# 1_XBEE_Interface.net
KiCad netlist of a schematic drawn in Altium Designer
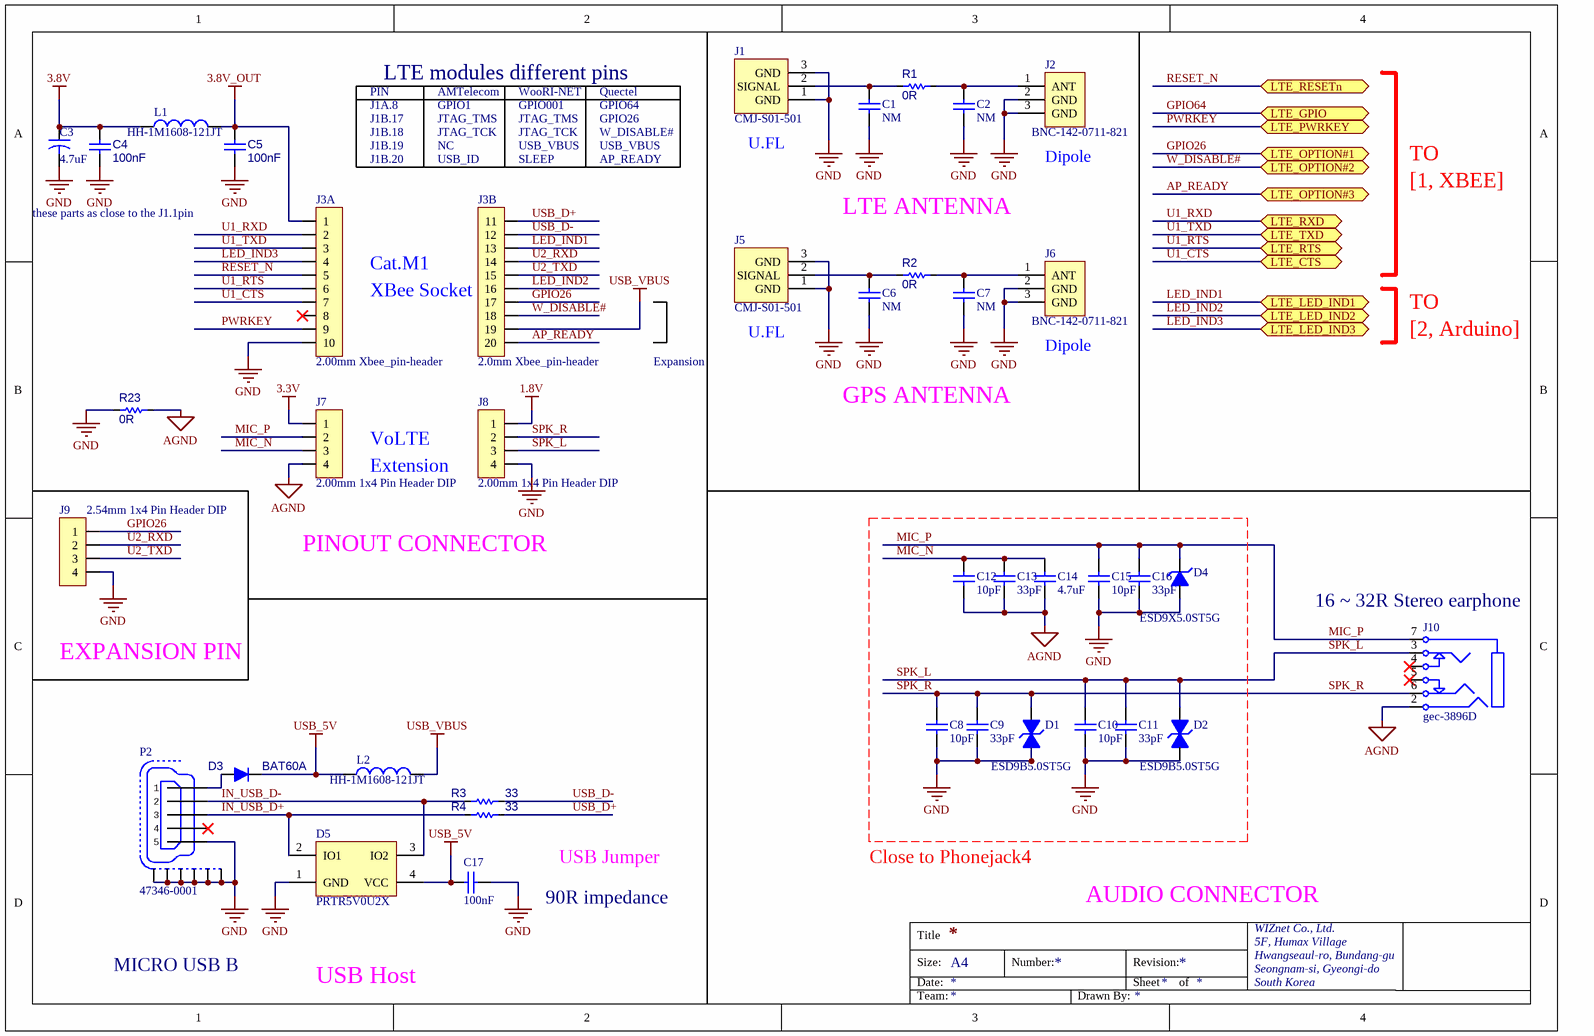
[diagram p0: 1.XBEE Interface.SchDoc]

(export (version "E")
  (design (tool "Eeschema 10.0.6"))
  (components
    (comp (ref "C1")
      (value "NM")
      (footprint "CAP-0402")
      (description "Ceramic CAP 0402(1005)")
      (libsource (lib "Edward") (part "CAP-0402"))
    )
    (comp (ref "C2")
      (value "NM")
      (footprint "CAP-0402")
      (description "Ceramic CAP 0402(1005)")
      (libsource (lib "Edward") (part "CAP-0402"))
    )
    (comp (ref "C3")
      (value "4.7uF")
      (footprint "CAP-A Size")
      (description "Electrolytic Capacitors")
      (libsource (lib "Quectel_IF_Board") (part "CAP"))
    )
    (comp (ref "C4")
      (value "100nF")
      (footprint "CAP-0603")
      (description "Ceramic CAP 0603(1608)")
      (libsource (lib "Scott_lib") (part "CAP-0603"))
    )
    (comp (ref "C5")
      (value "100nF")
      (footprint "CAP-0603")
      (description "Ceramic CAP 0603(1608)")
      (libsource (lib "Scott_lib") (part "CAP-0603"))
    )
    (comp (ref "C6")
      (value "NM")
      (footprint "CAP-0402")
      (description "Ceramic CAP 0402(1005)")
      (libsource (lib "Edward") (part "CAP-0402"))
    )
    (comp (ref "C7")
      (value "NM")
      (footprint "CAP-0402")
      (description "Ceramic CAP 0402(1005)")
      (libsource (lib "Edward") (part "CAP-0402"))
    )
    (comp (ref "C8")
      (value "10pF")
      (footprint "CAP-0402")
      (description "Ceramic CAP 0402(1005)")
      (libsource (lib "Edward") (part "CAP-0402"))
    )
    (comp (ref "C9")
      (value "33pF")
      (footprint "CAP-0402")
      (description "Ceramic CAP 0402(1005)")
      (libsource (lib "Edward") (part "CAP-0402"))
    )
    (comp (ref "C10")
      (value "10pF")
      (footprint "CAP-0402")
      (description "Ceramic CAP 0402(1005)")
      (libsource (lib "Edward") (part "CAP-0402"))
    )
    (comp (ref "C11")
      (value "33pF")
      (footprint "CAP-0402")
      (description "Ceramic CAP 0402(1005)")
      (libsource (lib "Edward") (part "CAP-0402"))
    )
    (comp (ref "C12")
      (value "10pF")
      (footprint "CAP-0402")
      (description "Ceramic CAP 0402(1005)")
      (libsource (lib "Edward") (part "CAP-0402"))
    )
    (comp (ref "C13")
      (value "33pF")
      (footprint "CAP-0402")
      (description "Ceramic CAP 0402(1005)")
      (libsource (lib "Edward") (part "CAP-0402"))
    )
    (comp (ref "C14")
      (value "4.7uF")
      (footprint "CAP-0603")
      (description "Ceramic CAP 0603(1608)")
      (libsource (lib "Edward") (part "CAP-0603"))
    )
    (comp (ref "C15")
      (value "10pF")
      (footprint "CAP-0402")
      (description "Ceramic CAP 0402(1005)")
      (libsource (lib "Edward") (part "CAP-0402"))
    )
    (comp (ref "C16")
      (value "33pF")
      (footprint "CAP-0402")
      (description "Ceramic CAP 0402(1005)")
      (libsource (lib "Edward") (part "CAP-0402"))
    )
    (comp (ref "C17")
      (value "100nF")
      (footprint "CAP-0402")
      (description "Ceramic CAP 0402")
      (libsource (lib "Scott_lib") (part "CAP-0805"))
    )
    (comp (ref "D1")
      (value "ESD9B5.0ST5G")
      (footprint "SOD-882(TVS)")
      (description "Bi-directional TVS diode")
      (libsource (lib "Edward") (part "PESD5V0S1BL"))
    )
    (comp (ref "D2")
      (value "ESD9B5.0ST5G")
      (footprint "SOD-882(TVS)")
      (description "Bi-directional TVS diode")
      (libsource (lib "Edward") (part "PESD5V0S1BL"))
    )
    (comp (ref "D3")
      (value "BAT60A")
      (footprint "SOD-323(1-C,2-A)")
      (description "Silicon Schottky Diode")
      (libsource (lib "Scott_lib") (part "DIODE-BAT60A"))
    )
    (comp (ref "D4")
      (value "ESD9X5.0ST5G")
      (footprint "SOD-923(1-C,2-A)")
      (description "Uni-directional TVS diode")
      (libsource (lib "Edward") (part "ESD9X5.0ST5G"))
    )
    (comp (ref "D5")
      (value "PRTR5V0U2X")
      (footprint "SOT-143")
      (description "Ultra low capacitance double rail-to-rail ESD protection diode")
      (fields
        (field (name "MANUFACTURER") "NXP")
        (field (name "2ND SOURCE PART NUMBER") "152-4157")
        (field (name "PUBLISHER") "Nordic Semiconductor")
      )
      (libsource (lib "Quectel_IF_Board") (part "PRTR5V0U2X"))
    )
    (comp (ref "J1")
      (value "CMJ-S01-501")
      (footprint "BNC-CMJ-S01-501")
      (description "U.FL CONNECTOR")
      (libsource (lib "Edward") (part "U.FL CONNECTOR"))
    )
    (comp (ref "J2")
      (value "BNC-142-0711-821")
      (footprint "BNC-142-0711-821")
      (description "SMA_Female")
      (libsource (lib "Edward") (part "SMA_Female"))
    )
    (comp (ref "J3")
      (value "2.00mm Xbee_pin-header")
      (footprint "XBEE(1)")
      (description "Xbee_pin-header, WizFi310, LoRa, LTE CAT M1")
      (libsource (lib "Edward") (part "Xbee_pin-header"))
    )
    (comp (ref "J5")
      (value "CMJ-S01-501")
      (footprint "BNC-CMJ-S01-501")
      (description "U.FL CONNECTOR")
      (libsource (lib "Edward") (part "U.FL CONNECTOR"))
    )
    (comp (ref "J6")
      (value "BNC-142-0711-821")
      (footprint "BNC-142-0711-821")
      (description "SMA_Female")
      (libsource (lib "Edward") (part "SMA_Female"))
    )
    (comp (ref "J7")
      (value "2.00mm 1x4 Pin Header DIP")
      (footprint "IDC-1X4(2MM)")
      (libsource (lib "Edward") (part "2.00mm 1x4 Pin Header DIP"))
    )
    (comp (ref "J8")
      (value "2.00mm 1x4 Pin Header DIP")
      (footprint "IDC-1X4(2MM)")
      (libsource (lib "") (part "2.00mm 1x4 Pin Header DIP_1"))
    )
    (comp (ref "J9")
      (value "2.54mm 1x4 Pin Header DIP")
      (footprint "IDC-1X4")
      (libsource (lib "Scott_lib") (part "2.54mm 1x4 Pin Header DIP"))
    )
    (comp (ref "J10")
      (value "gec-3896D")
      (footprint "PJ-3.5-3106")
      (description "3-Conductor Jack with 2 break contacts (normals) and 2 auxiliary make contacts")
      (fields (field (name "PUBLISHER") "Altium Limited"))
      (libsource (lib "Edward") (part "Phonejack 6"))
    )
    (comp (ref "L1")
      (value "HH-1M1608-121JT")
      (footprint "IND-0603")
      (description "Inductor 0603(1608)")
      (libsource (lib "WIZ750SR") (part "IND-0603"))
    )
    (comp (ref "L2")
      (value "HH-1M1608-121JT")
      (footprint "IND-0603")
      (description "Inductor 0603(1608)")
      (libsource (lib "WIZ750SR") (part "IND-0603"))
    )
    (comp (ref "P2")
      (value "47346-0001")
      (footprint "USB-MOLEX-47346")
      (description "MICRO USB B Type")
      (libsource (lib "Edward") (part "47346-0001"))
    )
    (comp (ref "R1")
      (value "0R")
      (footprint "RES-0402")
      (description "RES-0402")
      (libsource (lib "Edward") (part "RES-0402"))
    )
    (comp (ref "R2")
      (value "0R")
      (footprint "RES-0402")
      (description "RES-0402")
      (libsource (lib "Edward") (part "RES-0402"))
    )
    (comp (ref "R3")
      (value "33")
      (footprint "RES-0603")
      (description "RES0603")
      (libsource (lib "Scott_lib") (part "RES-0603"))
    )
    (comp (ref "R4")
      (value "33")
      (footprint "RES-0603")
      (description "RES0603")
      (libsource (lib "Scott_lib") (part "RES-0603"))
    )
    (comp (ref "R23")
      (value "0R")
      (footprint "RES-0603")
      (description "RES0603")
      (libsource (lib "Scott_lib") (part "RES-0603"))
    )
  )
  (nets
    (net (code "1") (name "/AP_READY") (class "Default")
      (node (ref "J3") (pin "20") (pinfunction "20_20") (pintype "passive"))
    )
    (net (code "2") (name "/GPIO26") (class "Default")
      (node (ref "J3") (pin "17") (pinfunction "17_17") (pintype "passive"))
      (node (ref "J9") (pin "1") (pinfunction "1_1") (pintype "passive"))
    )
    (net (code "4") (name "/IN_USB_D+") (class "Default")
      (node (ref "D5") (pin "2") (pinfunction "IO1_2") (pintype "passive"))
      (node (ref "P2") (pin "3") (pinfunction "3_3") (pintype "passive"))
      (node (ref "R4") (pin "2") (pinfunction "2_2") (pintype "passive"))
    )
    (net (code "5") (name "/IN_USB_D-") (class "Default")
      (node (ref "D5") (pin "3") (pinfunction "IO2_3") (pintype "passive"))
      (node (ref "P2") (pin "2") (pinfunction "2_2") (pintype "passive"))
      (node (ref "R3") (pin "2") (pinfunction "2_2") (pintype "passive"))
    )
    (net (code "6") (name "/LED_IND1") (class "Default")
      (node (ref "J3") (pin "13") (pinfunction "13_13") (pintype "passive"))
    )
    (net (code "7") (name "/LED_IND2") (class "Default")
      (node (ref "J3") (pin "16") (pinfunction "16_16") (pintype "passive"))
    )
    (net (code "8") (name "/LED_IND3") (class "Default")
      (node (ref "J3") (pin "4") (pinfunction "4_4") (pintype "passive"))
    )
    (net (code "9") (name "/MIC_N") (class "Default")
      (node (ref "C12") (pin "2") (pinfunction "2_2") (pintype "passive"))
      (node (ref "C13") (pin "2") (pinfunction "2_2") (pintype "passive"))
      (node (ref "C14") (pin "2") (pinfunction "2_2") (pintype "passive"))
      (node (ref "J7") (pin "3") (pinfunction "3_3") (pintype "passive"))
    )
    (net (code "10") (name "/MIC_P") (class "Default")
      (node (ref "C15") (pin "2") (pinfunction "2_2") (pintype "passive"))
      (node (ref "C16") (pin "2") (pinfunction "2_2") (pintype "passive"))
      (node (ref "D4") (pin "1") (pinfunction "1_1") (pintype "passive"))
      (node (ref "J10") (pin "7") (pinfunction "7_7") (pintype "passive"))
      (node (ref "J7") (pin "2") (pinfunction "2_2") (pintype "passive"))
    )
    (net (code "11") (name "/PWRKEY") (class "Default")
      (node (ref "J3") (pin "9") (pinfunction "9_9") (pintype "passive"))
    )
    (net (code "12") (name "/RESET_N") (class "Default")
      (node (ref "J3") (pin "5") (pinfunction "5_5") (pintype "passive"))
    )
    (net (code "13") (name "/SPK_L") (class "Default")
      (node (ref "C10") (pin "2") (pinfunction "2_2") (pintype "passive"))
      (node (ref "C11") (pin "2") (pinfunction "2_2") (pintype "passive"))
      (node (ref "D2") (pin "1") (pinfunction "1_1") (pintype "passive"))
      (node (ref "J10") (pin "3") (pinfunction "3_3") (pintype "passive"))
      (node (ref "J8") (pin "3") (pinfunction "3_3") (pintype "passive"))
    )
    (net (code "14") (name "/SPK_R") (class "Default")
      (node (ref "C8") (pin "2") (pinfunction "2_2") (pintype "passive"))
      (node (ref "C9") (pin "2") (pinfunction "2_2") (pintype "passive"))
      (node (ref "D1") (pin "1") (pinfunction "1_1") (pintype "passive"))
      (node (ref "J10") (pin "6") (pinfunction "6_6") (pintype "passive"))
      (node (ref "J8") (pin "2") (pinfunction "2_2") (pintype "passive"))
    )
    (net (code "15") (name "/U1_CTS") (class "Default")
      (node (ref "J3") (pin "7") (pinfunction "7_7") (pintype "passive"))
    )
    (net (code "16") (name "/U1_RTS") (class "Default")
      (node (ref "J3") (pin "6") (pinfunction "6_6") (pintype "passive"))
    )
    (net (code "17") (name "/U1_RXD") (class "Default")
      (node (ref "J3") (pin "2") (pinfunction "2_2") (pintype "passive"))
    )
    (net (code "18") (name "/U1_TXD") (class "Default")
      (node (ref "J3") (pin "3") (pinfunction "3_3") (pintype "passive"))
    )
    (net (code "19") (name "/U2_RXD") (class "Default")
      (node (ref "J3") (pin "14") (pinfunction "14_14") (pintype "passive"))
      (node (ref "J9") (pin "2") (pinfunction "2_2") (pintype "passive"))
    )
    (net (code "20") (name "/U2_TXD") (class "Default")
      (node (ref "J3") (pin "15") (pinfunction "15_15") (pintype "passive"))
      (node (ref "J9") (pin "3") (pinfunction "3_3") (pintype "passive"))
    )
    (net (code "21") (name "/USB_D+") (class "Default")
      (node (ref "J3") (pin "11") (pinfunction "11_11") (pintype "passive"))
      (node (ref "R4") (pin "1") (pinfunction "1_1") (pintype "passive"))
    )
    (net (code "22") (name "/USB_D-") (class "Default")
      (node (ref "J3") (pin "12") (pinfunction "12_12") (pintype "passive"))
      (node (ref "R3") (pin "1") (pinfunction "1_1") (pintype "passive"))
    )
    (net (code "23") (name "/W_DISABLE#") (class "Default")
      (node (ref "J3") (pin "18") (pinfunction "18_18") (pintype "passive"))
    )
    (net (code "24") (name "1.8V") (class "Default")
      (node (ref "J8") (pin "1") (pinfunction "1_1") (pintype "passive"))
    )
    (net (code "25") (name "3.3V") (class "Default")
      (node (ref "J7") (pin "1") (pinfunction "1_1") (pintype "passive"))
    )
    (net (code "26") (name "3.8V") (class "Default")
      (node (ref "C3") (pin "1") (pinfunction "1_1") (pintype "passive"))
      (node (ref "C4") (pin "1") (pinfunction "1_1") (pintype "passive"))
      (node (ref "L1") (pin "1") (pinfunction "1_1") (pintype "passive"))
    )
    (net (code "27") (name "3.8V_OUT") (class "Default")
      (node (ref "C5") (pin "1") (pinfunction "1_1") (pintype "passive"))
      (node (ref "J3") (pin "1") (pinfunction "1_1") (pintype "passive"))
      (node (ref "L1") (pin "2") (pinfunction "2_2") (pintype "passive"))
    )
    (net (code "28") (name "AGND") (class "Default")
      (node (ref "C12") (pin "1") (pinfunction "1_1") (pintype "passive"))
      (node (ref "C13") (pin "1") (pinfunction "1_1") (pintype "passive"))
      (node (ref "C14") (pin "1") (pinfunction "1_1") (pintype "passive"))
      (node (ref "J10") (pin "2") (pinfunction "2_2") (pintype "passive"))
      (node (ref "J7") (pin "4") (pinfunction "4_4") (pintype "passive"))
      (node (ref "R23") (pin "2") (pinfunction "2_2") (pintype "passive"))
    )
    (net (code "29") (name "GND") (class "Default")
      (node (ref "C1") (pin "1") (pinfunction "1_1") (pintype "passive"))
      (node (ref "C10") (pin "1") (pinfunction "1_1") (pintype "passive"))
      (node (ref "C11") (pin "1") (pinfunction "1_1") (pintype "passive"))
      (node (ref "C15") (pin "1") (pinfunction "1_1") (pintype "passive"))
      (node (ref "C16") (pin "1") (pinfunction "1_1") (pintype "passive"))
      (node (ref "C17") (pin "2") (pinfunction "2_2") (pintype "passive"))
      (node (ref "C2") (pin "1") (pinfunction "1_1") (pintype "passive"))
      (node (ref "C3") (pin "2") (pinfunction "2_2") (pintype "passive"))
      (node (ref "C4") (pin "2") (pinfunction "2_2") (pintype "passive"))
      (node (ref "C5") (pin "2") (pinfunction "2_2") (pintype "passive"))
      (node (ref "C6") (pin "1") (pinfunction "1_1") (pintype "passive"))
      (node (ref "C7") (pin "1") (pinfunction "1_1") (pintype "passive"))
      (node (ref "C8") (pin "1") (pinfunction "1_1") (pintype "passive"))
      (node (ref "C9") (pin "1") (pinfunction "1_1") (pintype "passive"))
      (node (ref "D1") (pin "2") (pinfunction "2_2") (pintype "passive"))
      (node (ref "D2") (pin "2") (pinfunction "2_2") (pintype "passive"))
      (node (ref "D4") (pin "2") (pinfunction "2_2") (pintype "passive"))
      (node (ref "D5") (pin "1") (pinfunction "GND_1") (pintype "passive"))
      (node (ref "J1") (pin "1") (pinfunction "GND_1") (pintype "passive"))
      (node (ref "J1") (pin "3") (pinfunction "GND_3") (pintype "passive"))
      (node (ref "J2") (pin "2") (pinfunction "GND_2") (pintype "power_in"))
      (node (ref "J2") (pin "3") (pinfunction "GND_3") (pintype "power_in"))
      (node (ref "J3") (pin "10") (pinfunction "10_10") (pintype "passive"))
      (node (ref "J5") (pin "1") (pinfunction "GND_1") (pintype "passive"))
      (node (ref "J5") (pin "3") (pinfunction "GND_3") (pintype "passive"))
      (node (ref "J6") (pin "2") (pinfunction "GND_2") (pintype "power_in"))
      (node (ref "J6") (pin "3") (pinfunction "GND_3") (pintype "power_in"))
      (node (ref "J8") (pin "4") (pinfunction "4_4") (pintype "passive"))
      (node (ref "J9") (pin "4") (pinfunction "4_4") (pintype "passive"))
      (node (ref "P2") (pin "10") (pinfunction "10_10") (pintype "passive"))
      (node (ref "P2") (pin "11") (pinfunction "11_11") (pintype "passive"))
      (node (ref "P2") (pin "5") (pinfunction "5_5") (pintype "passive"))
      (node (ref "P2") (pin "6") (pinfunction "6_6") (pintype "passive"))
      (node (ref "P2") (pin "7") (pinfunction "7_7") (pintype "passive"))
      (node (ref "P2") (pin "8") (pinfunction "8_8") (pintype "passive"))
      (node (ref "P2") (pin "9") (pinfunction "9_9") (pintype "passive"))
      (node (ref "R23") (pin "1") (pinfunction "1_1") (pintype "passive"))
    )
    (net (code "30") (name "Net-(D3-A)") (class "Default")
      (node (ref "D3") (pin "2") (pinfunction "A_2") (pintype "passive"))
      (node (ref "P2") (pin "1") (pinfunction "1_1") (pintype "passive"))
    )
    (net (code "31") (name "Net-(J1-SIGNAL)") (class "Default")
      (node (ref "C1") (pin "2") (pinfunction "2_2") (pintype "passive"))
      (node (ref "J1") (pin "2") (pinfunction "SIGNAL_2") (pintype "passive"))
      (node (ref "R1") (pin "1") (pinfunction "1_1") (pintype "passive"))
    )
    (net (code "32") (name "Net-(J2-ANT)") (class "Default")
      (node (ref "C2") (pin "2") (pinfunction "2_2") (pintype "passive"))
      (node (ref "J2") (pin "1") (pinfunction "ANT_1") (pintype "passive"))
      (node (ref "R1") (pin "2") (pinfunction "2_2") (pintype "passive"))
    )
    (net (code "33") (name "Net-(J5-SIGNAL)") (class "Default")
      (node (ref "C6") (pin "2") (pinfunction "2_2") (pintype "passive"))
      (node (ref "J5") (pin "2") (pinfunction "SIGNAL_2") (pintype "passive"))
      (node (ref "R2") (pin "1") (pinfunction "1_1") (pintype "passive"))
    )
    (net (code "34") (name "Net-(J6-ANT)") (class "Default")
      (node (ref "C7") (pin "2") (pinfunction "2_2") (pintype "passive"))
      (node (ref "J6") (pin "1") (pinfunction "ANT_1") (pintype "passive"))
      (node (ref "R2") (pin "2") (pinfunction "2_2") (pintype "passive"))
    )
    (net (code "35") (name "USB_5V") (class "Default")
      (node (ref "C17") (pin "1") (pinfunction "1_1") (pintype "passive"))
      (node (ref "D3") (pin "1") (pinfunction "K_1") (pintype "passive"))
      (node (ref "D5") (pin "4") (pinfunction "VCC_4") (pintype "passive"))
      (node (ref "L2") (pin "1") (pinfunction "1_1") (pintype "passive"))
    )
    (net (code "36") (name "USB_VBUS") (class "Default")
      (node (ref "J3") (pin "19") (pinfunction "19_19") (pintype "passive"))
      (node (ref "L2") (pin "2") (pinfunction "2_2") (pintype "passive"))
    )
    (net (code "37") (name "unconnected-(J3-Pad8)") (class "Default")
      (node (ref "J3") (pin "8") (pinfunction "8_8") (pintype "passive+no_connect"))
    )
    (net (code "38") (name "unconnected-(J10-Pad4)") (class "Default")
      (node (ref "J10") (pin "4") (pinfunction "4_4") (pintype "passive+no_connect"))
    )
    (net (code "39") (name "unconnected-(J10-Pad5)") (class "Default")
      (node (ref "J10") (pin "5") (pinfunction "5_5") (pintype "passive+no_connect"))
    )
    (net (code "40") (name "unconnected-(P2-Pad4)") (class "Default")
      (node (ref "P2") (pin "4") (pinfunction "4_4") (pintype "passive+no_connect"))
    )
  )
)
